# carte-cool.net
KiCad netlist of a schematic drawn in EAGLE
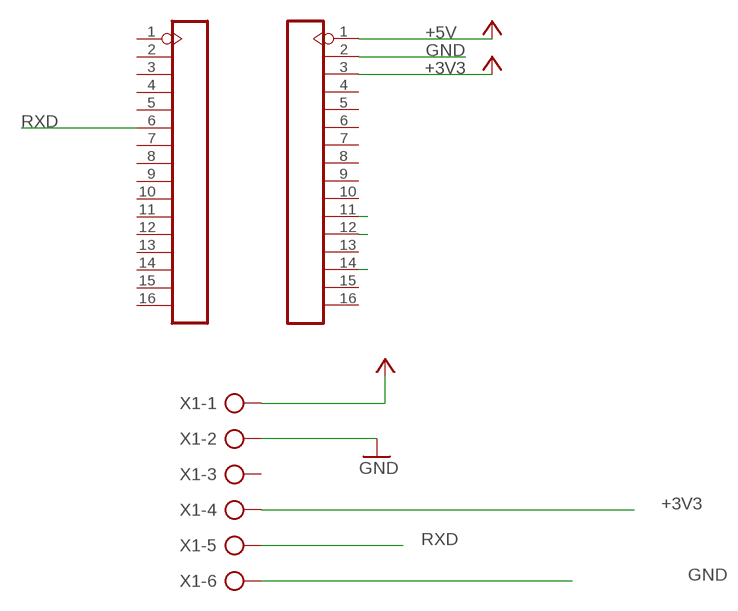
[diagram p0: schematic, sheet 1]

(export (version "E")
  (design (tool "Eeschema 10.0.6"))
  (components
    (comp (ref "J1")
      (value "16p-2.54")
      (footprint "eagle-import:H16-2.54")
      (fields (field (name "MPN") "P125-1116A0BS116AX"))
      (libsource (lib "eagle-import") (part "DIP-BLACK-MALE-HEADER-VERT(16P-2.54)"))
    )
    (comp (ref "J2")
      (value "16p-2.54")
      (footprint "eagle-import:H16-2.54")
      (fields (field (name "MPN") "P125-1116A0BS116AX"))
      (libsource (lib "eagle-import") (part "DIP-BLACK-MALE-HEADER-VERT(16P-2.54)"))
    )
    (comp (ref "X1")
      (value "AK500/6-H")
      (footprint "eagle-import:AK500_6-H")
      (libsource (lib "eagle-import") (part "AK500/6-H"))
    )
  )
  (nets
    (net (code "1") (name "+3V3") (class "Default")
      (node (ref "J2") (pin "3") (pinfunction "3_3") (pintype "passive"))
      (node (ref "X1") (pin "4") (pinfunction "KL_4") (pintype "passive"))
    )
    (net (code "2") (name "+5V") (class "Default")
      (node (ref "J2") (pin "1") (pinfunction "1_1") (pintype "passive"))
      (node (ref "X1") (pin "1") (pinfunction "KL_1") (pintype "passive"))
    )
    (net (code "3") (name "GND") (class "Default")
      (node (ref "J2") (pin "2") (pinfunction "2_2") (pintype "passive"))
      (node (ref "X1") (pin "2") (pinfunction "KL_2") (pintype "passive"))
      (node (ref "X1") (pin "6") (pinfunction "KL_6") (pintype "passive"))
    )
    (net (code "4") (name "RXD") (class "Default")
      (node (ref "J1") (pin "6") (pinfunction "6_6") (pintype "passive"))
      (node (ref "X1") (pin "5") (pinfunction "KL_5") (pintype "passive"))
    )
    (net (code "5") (name "unconnected-(J1-Pad1)") (class "Default")
      (node (ref "J1") (pin "1") (pinfunction "1_1") (pintype "passive"))
    )
    (net (code "6") (name "unconnected-(J1-Pad2)") (class "Default")
      (node (ref "J1") (pin "2") (pinfunction "2_2") (pintype "passive"))
    )
    (net (code "7") (name "unconnected-(J1-Pad3)") (class "Default")
      (node (ref "J1") (pin "3") (pinfunction "3_3") (pintype "passive"))
    )
    (net (code "8") (name "unconnected-(J1-Pad4)") (class "Default")
      (node (ref "J1") (pin "4") (pinfunction "4_4") (pintype "passive"))
    )
    (net (code "9") (name "unconnected-(J1-Pad5)") (class "Default")
      (node (ref "J1") (pin "5") (pinfunction "5_5") (pintype "passive"))
    )
    (net (code "10") (name "unconnected-(J1-Pad7)") (class "Default")
      (node (ref "J1") (pin "7") (pinfunction "7_7") (pintype "passive"))
    )
    (net (code "11") (name "unconnected-(J1-Pad8)") (class "Default")
      (node (ref "J1") (pin "8") (pinfunction "8_8") (pintype "passive"))
    )
    (net (code "12") (name "unconnected-(J1-Pad9)") (class "Default")
      (node (ref "J1") (pin "9") (pinfunction "9_9") (pintype "passive"))
    )
    (net (code "13") (name "unconnected-(J1-Pad10)") (class "Default")
      (node (ref "J1") (pin "10") (pinfunction "10_10") (pintype "passive"))
    )
    (net (code "14") (name "unconnected-(J1-Pad11)") (class "Default")
      (node (ref "J1") (pin "11") (pinfunction "11_11") (pintype "passive"))
    )
    (net (code "15") (name "unconnected-(J1-Pad12)") (class "Default")
      (node (ref "J1") (pin "12") (pinfunction "12_12") (pintype "passive"))
    )
    (net (code "16") (name "unconnected-(J1-Pad13)") (class "Default")
      (node (ref "J1") (pin "13") (pinfunction "13_13") (pintype "passive"))
    )
    (net (code "17") (name "unconnected-(J1-Pad14)") (class "Default")
      (node (ref "J1") (pin "14") (pinfunction "14_14") (pintype "passive"))
    )
    (net (code "18") (name "unconnected-(J1-Pad15)") (class "Default")
      (node (ref "J1") (pin "15") (pinfunction "15_15") (pintype "passive"))
    )
    (net (code "19") (name "unconnected-(J1-Pad16)") (class "Default")
      (node (ref "J1") (pin "16") (pinfunction "16_16") (pintype "passive"))
    )
    (net (code "20") (name "unconnected-(J2-Pad4)") (class "Default")
      (node (ref "J2") (pin "4") (pinfunction "4_4") (pintype "passive"))
    )
    (net (code "21") (name "unconnected-(J2-Pad5)") (class "Default")
      (node (ref "J2") (pin "5") (pinfunction "5_5") (pintype "passive"))
    )
    (net (code "22") (name "unconnected-(J2-Pad6)") (class "Default")
      (node (ref "J2") (pin "6") (pinfunction "6_6") (pintype "passive"))
    )
    (net (code "23") (name "unconnected-(J2-Pad7)") (class "Default")
      (node (ref "J2") (pin "7") (pinfunction "7_7") (pintype "passive"))
    )
    (net (code "24") (name "unconnected-(J2-Pad8)") (class "Default")
      (node (ref "J2") (pin "8") (pinfunction "8_8") (pintype "passive"))
    )
    (net (code "25") (name "unconnected-(J2-Pad9)") (class "Default")
      (node (ref "J2") (pin "9") (pinfunction "9_9") (pintype "passive"))
    )
    (net (code "26") (name "unconnected-(J2-Pad10)") (class "Default")
      (node (ref "J2") (pin "10") (pinfunction "10_10") (pintype "passive"))
    )
    (net (code "27") (name "unconnected-(J2-Pad11)") (class "Default")
      (node (ref "J2") (pin "11") (pinfunction "11_11") (pintype "passive"))
    )
    (net (code "28") (name "unconnected-(J2-Pad12)") (class "Default")
      (node (ref "J2") (pin "12") (pinfunction "12_12") (pintype "passive"))
    )
    (net (code "29") (name "unconnected-(J2-Pad13)") (class "Default")
      (node (ref "J2") (pin "13") (pinfunction "13_13") (pintype "passive"))
    )
    (net (code "30") (name "unconnected-(J2-Pad14)") (class "Default")
      (node (ref "J2") (pin "14") (pinfunction "14_14") (pintype "passive"))
    )
    (net (code "31") (name "unconnected-(J2-Pad15)") (class "Default")
      (node (ref "J2") (pin "15") (pinfunction "15_15") (pintype "passive"))
    )
    (net (code "32") (name "unconnected-(J2-Pad16)") (class "Default")
      (node (ref "J2") (pin "16") (pinfunction "16_16") (pintype "passive"))
    )
    (net (code "33") (name "unconnected-(X1C-KL-Pad3)") (class "Default")
      (node (ref "X1") (pin "3") (pinfunction "KL_3") (pintype "passive"))
    )
  )
)
